# PCB_Gabri1_1_1.net
KiCad netlist of a schematic drawn in EAGLE
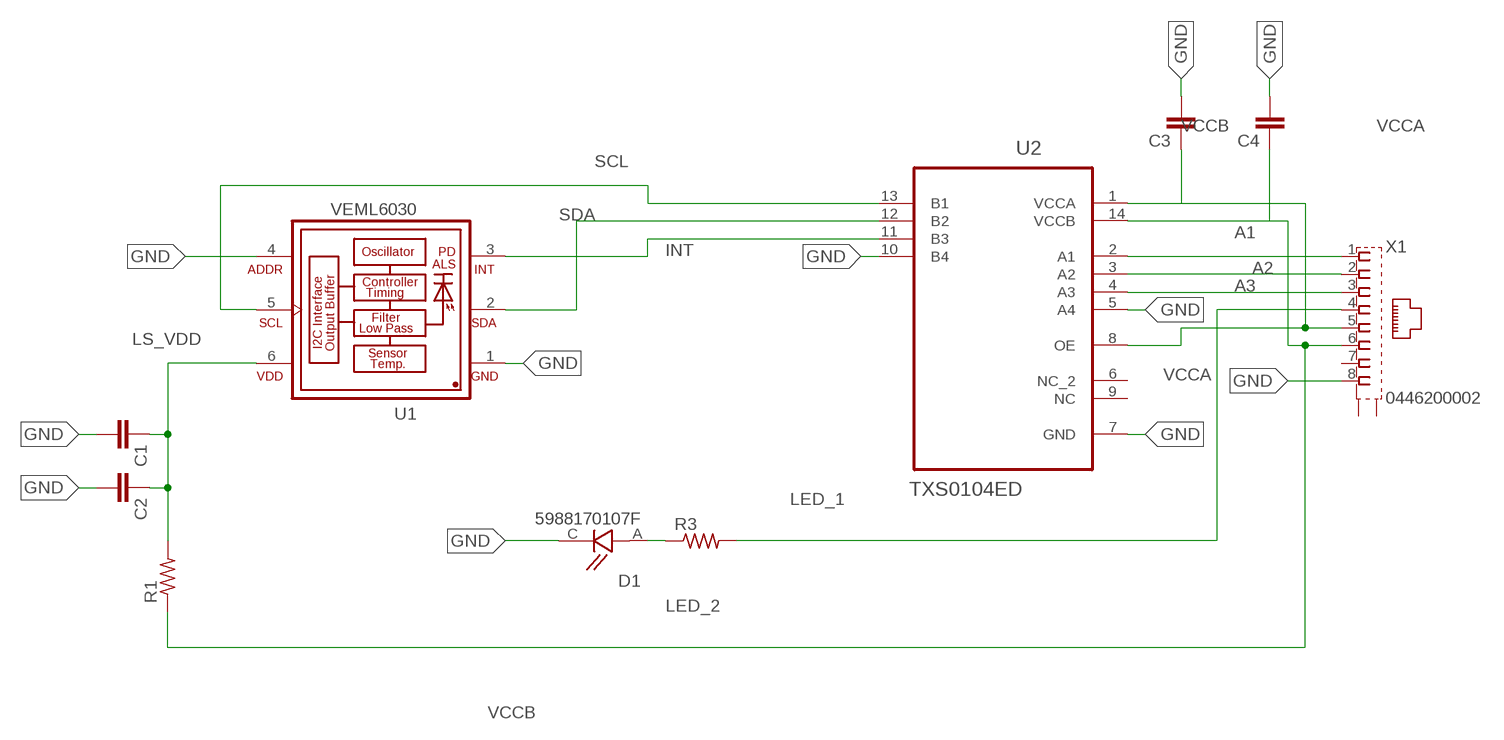
[diagram p0: schematic, sheet 1]

(export (version "E")
  (design (tool "Eeschema 10.0.6"))
  (components
    (comp (ref "C1")
      (value "C-EU025-024X044")
      (footprint "eagle-import:C025-024X044")
      (libsource (lib "eagle-import") (part "C-EU025-024X044"))
    )
    (comp (ref "C2")
      (value "C-EU025-024X044")
      (footprint "eagle-import:C025-024X044")
      (libsource (lib "eagle-import") (part "C-EU025-024X044"))
    )
    (comp (ref "C3")
      (value "C-EU025-024X044")
      (footprint "eagle-import:C025-024X044")
      (libsource (lib "eagle-import") (part "C-EU025-024X044"))
    )
    (comp (ref "C4")
      (value "C-EU025-024X044")
      (footprint "eagle-import:C025-024X044")
      (libsource (lib "eagle-import") (part "C-EU025-024X044"))
    )
    (comp (ref "D1")
      (value "5988170107F")
      (footprint "eagle-import:LEDC2012X70N")
      (fields (field (name "MF") "Dialight"))
      (libsource (lib "eagle-import") (part "5988170107F"))
    )
    (comp (ref "R1")
      (value "R-US_R0805")
      (footprint "eagle-import:R0805")
      (libsource (lib "eagle-import") (part "R-US_R0805"))
    )
    (comp (ref "R3")
      (value "R-US_R0805")
      (footprint "eagle-import:R0805")
      (libsource (lib "eagle-import") (part "R-US_R0805"))
    )
    (comp (ref "U1")
      (value "VEML6030")
      (footprint "eagle-import:VISHAY_VEML6030_2X2X0.87")
      (fields (field (name "MF") "Vishay"))
      (libsource (lib "eagle-import") (part "VEML6030"))
    )
    (comp (ref "U2")
      (value "TXS0104ED")
      (footprint "eagle-import:SOIC127P600X175-14N")
      (fields (field (name "MF") "Texas Instruments"))
      (libsource (lib "eagle-import") (part "TXS0104ED"))
    )
    (comp (ref "X1")
      (value "0446200002")
      (footprint "eagle-import:0446200002")
      (fields (field (name "MF") "Molex, LLC"))
      (libsource (lib "eagle-import") (part "0446200002"))
    )
  )
  (nets
    (net (code "1") (name "/A1") (class "Default")
      (node (ref "U2") (pin "2") (pinfunction "A1_2") (pintype "input"))
      (node (ref "X1") (pin "1") (pinfunction "1_1") (pintype "passive"))
    )
    (net (code "2") (name "/A2") (class "Default")
      (node (ref "U2") (pin "3") (pinfunction "A2_3") (pintype "input"))
      (node (ref "X1") (pin "2") (pinfunction "2_2") (pintype "passive"))
    )
    (net (code "3") (name "/A3") (class "Default")
      (node (ref "U2") (pin "4") (pinfunction "A3_4") (pintype "input"))
      (node (ref "X1") (pin "3") (pinfunction "3_3") (pintype "passive"))
    )
    (net (code "4") (name "/INT") (class "Default")
      (node (ref "U1") (pin "3") (pinfunction "INT_3") (pintype "output"))
      (node (ref "U2") (pin "11") (pinfunction "B3_11") (pintype "output"))
    )
    (net (code "5") (name "/LED_1") (class "Default")
      (node (ref "R3") (pin "2") (pinfunction "2_2") (pintype "passive"))
      (node (ref "X1") (pin "4") (pinfunction "4_4") (pintype "passive"))
    )
    (net (code "6") (name "/LED_2") (class "Default")
      (node (ref "D1") (pin "A") (pinfunction "A_A") (pintype "passive"))
      (node (ref "R3") (pin "1") (pinfunction "1_1") (pintype "passive"))
    )
    (net (code "7") (name "/LS_VDD") (class "Default")
      (node (ref "C1") (pin "1") (pinfunction "1_1") (pintype "passive"))
      (node (ref "C2") (pin "1") (pinfunction "1_1") (pintype "passive"))
      (node (ref "R1") (pin "2") (pinfunction "2_2") (pintype "passive"))
      (node (ref "U1") (pin "6") (pinfunction "VDD_6") (pintype "power_in"))
    )
    (net (code "8") (name "/SCL") (class "Default")
      (node (ref "U1") (pin "5") (pinfunction "SCL_5") (pintype "input"))
      (node (ref "U2") (pin "13") (pinfunction "B1_13") (pintype "output"))
    )
    (net (code "9") (name "/SDA") (class "Default")
      (node (ref "U1") (pin "2") (pinfunction "SDA_2") (pintype "bidirectional"))
      (node (ref "U2") (pin "12") (pinfunction "B2_12") (pintype "output"))
    )
    (net (code "10") (name "/VCCA") (class "Default")
      (node (ref "C3") (pin "1") (pinfunction "1_1") (pintype "passive"))
      (node (ref "U2") (pin "1") (pinfunction "VCCA_1") (pintype "power_in"))
      (node (ref "U2") (pin "8") (pinfunction "OE_8") (pintype "input"))
      (node (ref "X1") (pin "5") (pinfunction "5_5") (pintype "passive"))
    )
    (net (code "11") (name "/VCCB") (class "Default")
      (node (ref "C4") (pin "1") (pinfunction "1_1") (pintype "passive"))
      (node (ref "R1") (pin "1") (pinfunction "1_1") (pintype "passive"))
      (node (ref "U2") (pin "14") (pinfunction "VCCB_14") (pintype "power_in"))
      (node (ref "X1") (pin "6") (pinfunction "6_6") (pintype "passive"))
    )
    (net (code "12") (name "GND") (class "Default")
      (node (ref "C1") (pin "2") (pinfunction "2_2") (pintype "passive"))
      (node (ref "C2") (pin "2") (pinfunction "2_2") (pintype "passive"))
      (node (ref "C3") (pin "2") (pinfunction "2_2") (pintype "passive"))
      (node (ref "C4") (pin "2") (pinfunction "2_2") (pintype "passive"))
      (node (ref "D1") (pin "C") (pinfunction "C_C") (pintype "passive"))
      (node (ref "U1") (pin "1") (pinfunction "GND_1") (pintype "power_in"))
      (node (ref "U1") (pin "4") (pinfunction "ADDR_4") (pintype "bidirectional"))
      (node (ref "U2") (pin "10") (pinfunction "B4_10") (pintype "output"))
      (node (ref "U2") (pin "5") (pinfunction "A4_5") (pintype "input"))
      (node (ref "U2") (pin "7") (pinfunction "GND_7") (pintype "passive"))
      (node (ref "X1") (pin "8") (pinfunction "8_8") (pintype "passive"))
    )
    (net (code "13") (name "unconnected-(U2-NC-Pad9)") (class "Default")
      (node (ref "U2") (pin "9") (pinfunction "NC_9") (pintype "no_connect"))
    )
    (net (code "14") (name "unconnected-(U2-NC_2-Pad6)") (class "Default")
      (node (ref "U2") (pin "6") (pinfunction "NC_2_6") (pintype "no_connect"))
    )
    (net (code "15") (name "unconnected-(X1-Pad7)") (class "Default")
      (node (ref "X1") (pin "7") (pinfunction "7_7") (pintype "passive"))
    )
    (net (code "16") (name "unconnected-(X1-S1-PadS@1)") (class "Default")
      (node (ref "X1") (pin "S@1") (pinfunction "S1_S@1") (pintype "passive"))
    )
    (net (code "17") (name "unconnected-(X1-S2-PadS@2)") (class "Default")
      (node (ref "X1") (pin "S@2") (pinfunction "S2_S@2") (pintype "passive"))
    )
  )
)
